# tps63020-buck-boost-flashlight-driver-17.net
KiCad netlist of a schematic drawn in EAGLE
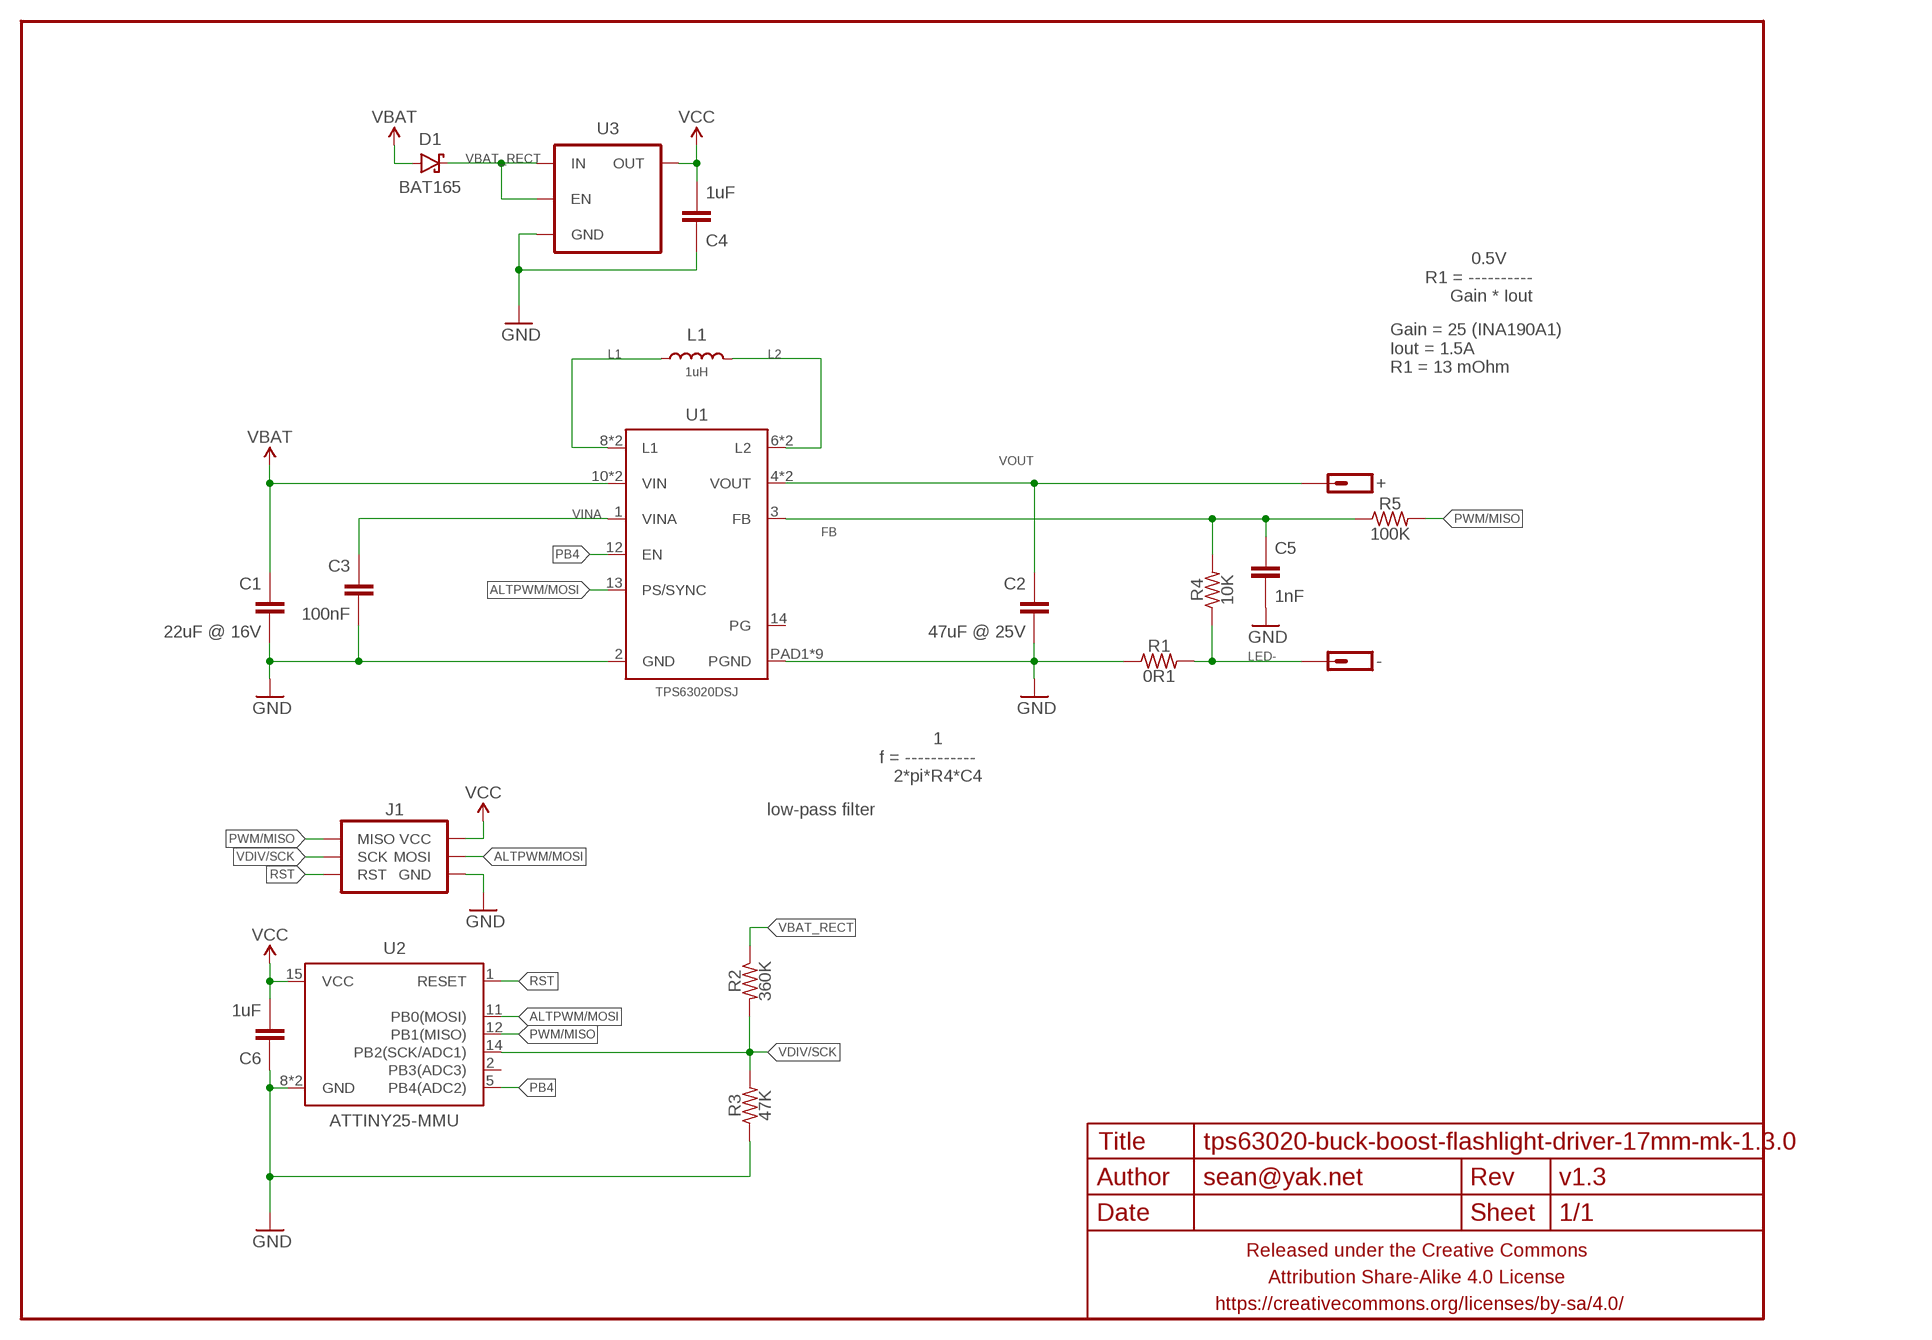
[diagram p0: schematic, sheet 1]

(export (version "E")
  (design (tool "Eeschema 10.0.6"))
  (components
    (comp (ref "+")
      (value "M01SMD-1.6MMX3.2MM")
      (footprint "eagle-import:1X01-SMD-1.6MMX3.2MM")
      (libsource (lib "eagle-import") (part "M01SMD-1.6MMX3.2MM"))
    )
    (comp (ref "-")
      (value "M01SMD-1.6MMX3.2MM")
      (footprint "eagle-import:1X01-SMD-1.6MMX3.2MM")
      (libsource (lib "eagle-import") (part "M01SMD-1.6MMX3.2MM"))
    )
    (comp (ref "C1")
      (value "22uF @ 16V")
      (footprint "eagle-import:C0805-TIGHTER")
      (libsource (lib "eagle-import") (part "CAPACITOR-CERAMICC0805-TIGHTER"))
    )
    (comp (ref "C2")
      (value "47uF @ 25V")
      (footprint "eagle-import:C1206")
      (libsource (lib "eagle-import") (part "CAPACITOR-CERAMICC1206"))
    )
    (comp (ref "C3")
      (value "100nF")
      (footprint "eagle-import:C0402")
      (libsource (lib "eagle-import") (part "CAPACITOR-CERAMICC0402"))
    )
    (comp (ref "C4")
      (value "1uF")
      (footprint "eagle-import:C0402")
      (libsource (lib "eagle-import") (part "CAPACITOR-CERAMICC0402"))
    )
    (comp (ref "C5")
      (value "1nF")
      (footprint "eagle-import:C0402")
      (libsource (lib "eagle-import") (part "CAPACITOR-CERAMICC0402"))
    )
    (comp (ref "C6")
      (value "1uF")
      (footprint "eagle-import:C0402")
      (libsource (lib "eagle-import") (part "CAPACITOR-CERAMICC0402"))
    )
    (comp (ref "D1")
      (value "BAT165")
      (footprint "eagle-import:SOD323-SCHOTTKY")
      (libsource (lib "eagle-import") (part "DIODE-SCHOTTKYSOD323"))
    )
    (comp (ref "FRAME1")
      (value "FRAME-LETTERNO_PACKAGE")
      (footprint "eagle-import:DUMMY")
      (fields
        (field (name "DESIGNER") "Nobody")
        (field (name "VERSION") "v01")
        (field (name "DESIGNER_1") "sean@yak.net")
        (field (name "VERSION_1") "v1.3")
      )
      (libsource (lib "eagle-import") (part "FRAME-LETTERNO_PACKAGE"))
    )
    (comp (ref "J1")
      (value "AVR_SPI_PRG_6SMD-1.27MM")
      (footprint "eagle-import:2X3-1.27MM-SMD")
      (libsource (lib "eagle-import") (part "AVR_SPI_PRG_6SMD-1.27MM"))
    )
    (comp (ref "L1")
      (value "1uH")
      (footprint "eagle-import:XAL50X0")
      (libsource (lib "eagle-import") (part "INDUCTORXAL50X0"))
    )
    (comp (ref "R1")
      (value "0R1")
      (footprint "eagle-import:R1206")
      (libsource (lib "eagle-import") (part "RESISTORR1206"))
    )
    (comp (ref "R2")
      (value "360K")
      (footprint "eagle-import:R0402")
      (libsource (lib "eagle-import") (part "RESISTORR0402"))
    )
    (comp (ref "R3")
      (value "47K")
      (footprint "eagle-import:R0402")
      (libsource (lib "eagle-import") (part "RESISTORR0402"))
    )
    (comp (ref "R4")
      (value "10K")
      (footprint "eagle-import:R0402")
      (libsource (lib "eagle-import") (part "RESISTORR0402"))
    )
    (comp (ref "R5")
      (value "100K")
      (footprint "eagle-import:R0402")
      (libsource (lib "eagle-import") (part "RESISTORR0402"))
    )
    (comp (ref "U1")
      (value "TPS63020DSJ")
      (footprint "eagle-import:VSON-14-4MMX3MM")
      (libsource (lib "eagle-import") (part "TPS63020DSJ"))
    )
    (comp (ref "U2")
      (value "ATTINY25-MMU")
      (footprint "eagle-import:QFN20")
      (libsource (lib "eagle-import") (part "ATTINY45TINY85-20-QFN"))
    )
    (comp (ref "U3")
      (value "V_REG_ENTLV700XXDCK-TIGHTER")
      (footprint "eagle-import:SC70-TIGHTER")
      (libsource (lib "eagle-import") (part "V_REG_ENTLV700XXDCK-TIGHTER"))
    )
  )
  (nets
    (net (code "1") (name "/FB") (class "Default")
      (node (ref "C5") (pin "1") (pinfunction "1_1") (pintype "passive"))
      (node (ref "R4") (pin "2") (pinfunction "2_2") (pintype "passive"))
      (node (ref "R5") (pin "1") (pinfunction "1_1") (pintype "passive"))
      (node (ref "U1") (pin "3") (pinfunction "FB_3") (pintype "bidirectional"))
    )
    (net (code "2") (name "/L1") (class "Default")
      (node (ref "L1") (pin "P$1") (pinfunction "1_P$1") (pintype "passive"))
      (node (ref "U1") (pin "8") (pinfunction "L1_8") (pintype "bidirectional"))
      (node (ref "U1") (pin "9") (pinfunction "L1_9") (pintype "bidirectional"))
    )
    (net (code "3") (name "/L2") (class "Default")
      (node (ref "L1") (pin "P$2") (pinfunction "2_P$2") (pintype "passive"))
      (node (ref "U1") (pin "6") (pinfunction "L2_6") (pintype "bidirectional"))
      (node (ref "U1") (pin "7") (pinfunction "L2_7") (pintype "bidirectional"))
    )
    (net (code "4") (name "/LED-") (class "Default")
      (node (ref "-") (pin "P$1") (pinfunction "1_P$1") (pintype "passive"))
      (node (ref "R1") (pin "2") (pinfunction "2_2") (pintype "passive"))
      (node (ref "R4") (pin "1") (pinfunction "1_1") (pintype "passive"))
    )
    (net (code "5") (name "/VINA") (class "Default")
      (node (ref "C3") (pin "1") (pinfunction "1_1") (pintype "passive"))
      (node (ref "U1") (pin "1") (pinfunction "VINA_1") (pintype "bidirectional"))
    )
    (net (code "6") (name "/VOUT") (class "Default")
      (node (ref "+") (pin "P$1") (pinfunction "1_P$1") (pintype "passive"))
      (node (ref "C2") (pin "1") (pinfunction "1_1") (pintype "passive"))
      (node (ref "U1") (pin "4") (pinfunction "VOUT_4") (pintype "bidirectional"))
      (node (ref "U1") (pin "5") (pinfunction "VOUT_5") (pintype "bidirectional"))
    )
    (net (code "7") (name "ALTPWM{slash}MOSI") (class "Default")
      (node (ref "J1") (pin "4") (pinfunction "MOSI_4") (pintype "passive"))
      (node (ref "U1") (pin "13") (pinfunction "PS/SYNC_13") (pintype "bidirectional"))
      (node (ref "U2") (pin "11") (pinfunction "PB0(MOSI)_11") (pintype "bidirectional"))
    )
    (net (code "8") (name "GND") (class "Default")
      (node (ref "C1") (pin "2") (pinfunction "2_2") (pintype "passive"))
      (node (ref "C2") (pin "2") (pinfunction "2_2") (pintype "passive"))
      (node (ref "C3") (pin "2") (pinfunction "2_2") (pintype "passive"))
      (node (ref "C4") (pin "1") (pinfunction "1_1") (pintype "passive"))
      (node (ref "C5") (pin "2") (pinfunction "2_2") (pintype "passive"))
      (node (ref "C6") (pin "1") (pinfunction "1_1") (pintype "passive"))
      (node (ref "J1") (pin "6") (pinfunction "GND_6") (pintype "passive"))
      (node (ref "R1") (pin "1") (pinfunction "1_1") (pintype "passive"))
      (node (ref "R3") (pin "1") (pinfunction "1_1") (pintype "passive"))
      (node (ref "U1") (pin "2") (pinfunction "GND_2") (pintype "bidirectional"))
      (node (ref "U1") (pin "PAD1") (pinfunction "PGND_PAD1") (pintype "bidirectional"))
      (node (ref "U1") (pin "PAD2") (pinfunction "PGND_PAD2") (pintype "bidirectional"))
      (node (ref "U1") (pin "PAD3") (pinfunction "PGND_PAD3") (pintype "bidirectional"))
      (node (ref "U1") (pin "PAD4") (pinfunction "PGND_PAD4") (pintype "bidirectional"))
      (node (ref "U1") (pin "PAD5") (pinfunction "PGND_PAD5") (pintype "bidirectional"))
      (node (ref "U1") (pin "PAD6") (pinfunction "PGND_PAD6") (pintype "bidirectional"))
      (node (ref "U1") (pin "PAD7") (pinfunction "PGND_PAD7") (pintype "bidirectional"))
      (node (ref "U1") (pin "PAD8") (pinfunction "PGND_PAD8") (pintype "bidirectional"))
      (node (ref "U1") (pin "PADCENTER") (pinfunction "PGND_PADCENTER") (pintype "bidirectional"))
      (node (ref "U2") (pin "8") (pinfunction "GND_8") (pintype "bidirectional"))
      (node (ref "U2") (pin "PAD") (pinfunction "GND_PAD") (pintype "bidirectional"))
      (node (ref "U3") (pin "2") (pinfunction "GND_2") (pintype "input"))
    )
    (net (code "9") (name "PB4") (class "Default")
      (node (ref "U1") (pin "12") (pinfunction "EN_12") (pintype "bidirectional"))
      (node (ref "U2") (pin "5") (pinfunction "PB4(ADC2)_5") (pintype "bidirectional"))
    )
    (net (code "10") (name "PWM{slash}MISO") (class "Default")
      (node (ref "J1") (pin "1") (pinfunction "MISO_1") (pintype "passive"))
      (node (ref "R5") (pin "2") (pinfunction "2_2") (pintype "passive"))
      (node (ref "U2") (pin "12") (pinfunction "PB1(MISO)_12") (pintype "bidirectional"))
    )
    (net (code "11") (name "RST") (class "Default")
      (node (ref "J1") (pin "5") (pinfunction "RST_5") (pintype "passive"))
      (node (ref "U2") (pin "1") (pinfunction "RESET_1") (pintype "bidirectional"))
    )
    (net (code "12") (name "VBAT") (class "Default")
      (node (ref "C1") (pin "1") (pinfunction "1_1") (pintype "passive"))
      (node (ref "D1") (pin "A") (pinfunction "A_A") (pintype "passive"))
      (node (ref "U1") (pin "10") (pinfunction "VIN_10") (pintype "bidirectional"))
      (node (ref "U1") (pin "11") (pinfunction "VIN_11") (pintype "bidirectional"))
    )
    (net (code "13") (name "VBAT_RECT") (class "Default")
      (node (ref "D1") (pin "C") (pinfunction "C_C") (pintype "passive"))
      (node (ref "R2") (pin "1") (pinfunction "1_1") (pintype "passive"))
      (node (ref "U3") (pin "1") (pinfunction "IN_1") (pintype "input"))
      (node (ref "U3") (pin "3") (pinfunction "EN_3") (pintype "input"))
    )
    (net (code "14") (name "VCC") (class "Default")
      (node (ref "C4") (pin "2") (pinfunction "2_2") (pintype "passive"))
      (node (ref "C6") (pin "2") (pinfunction "2_2") (pintype "passive"))
      (node (ref "J1") (pin "2") (pinfunction "VCC_2") (pintype "passive"))
      (node (ref "U2") (pin "15") (pinfunction "VCC_15") (pintype "bidirectional"))
      (node (ref "U3") (pin "5") (pinfunction "OUT_5") (pintype "passive"))
    )
    (net (code "15") (name "VDIV{slash}SCK") (class "Default")
      (node (ref "J1") (pin "3") (pinfunction "SCK_3") (pintype "passive"))
      (node (ref "R2") (pin "2") (pinfunction "2_2") (pintype "passive"))
      (node (ref "R3") (pin "2") (pinfunction "2_2") (pintype "passive"))
      (node (ref "U2") (pin "14") (pinfunction "PB2(SCK/ADC1)_14") (pintype "bidirectional"))
    )
    (net (code "16") (name "unconnected-(U1-PG-Pad14)") (class "Default")
      (node (ref "U1") (pin "14") (pinfunction "PG_14") (pintype "bidirectional"))
    )
    (net (code "17") (name "unconnected-(U2-PB3(ADC3)-Pad2)") (class "Default")
      (node (ref "U2") (pin "2") (pinfunction "PB3(ADC3)_2") (pintype "bidirectional"))
    )
  )
)
